# flash.net
KiCad netlist of a schematic drawn in Altium Designer
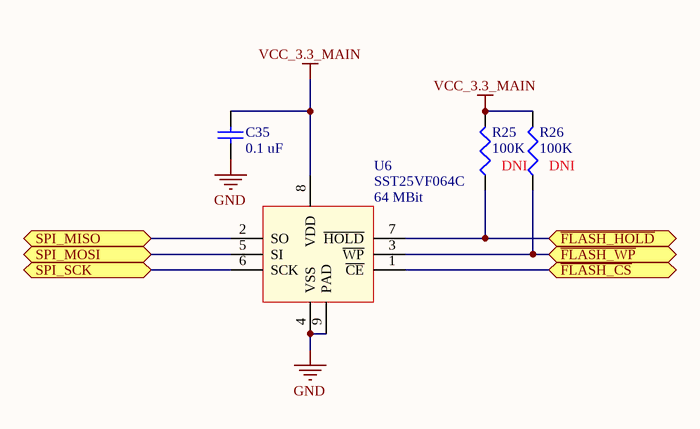
[diagram p0: flash.SchDoc]

(export (version "E")
  (design (tool "Eeschema 10.0.6"))
  (components
    (comp (ref "C35")
      (value "0.1 uF")
      (footprint "0402")
      (description "Ceramic capacitor, 0.1u, 0402 package")
      (fields (field (name "TOLERANCE") "10%") (field (name "Comment") "Ceramic capacitor"))
      (libsource (lib "rlc") (part "C_0.1u_10V_0402_ceramic"))
    )
    (comp (ref "R25")
      (value "100K")
      (footprint "0402")
      (description "Chip resistor, 100K, 0402 package")
      (fields (field (name "TOLERANCE") "1%") (field (name "POWER") "1/16 W"))
      (libsource (lib "rlc") (part "R_100K_0402"))
    )
    (comp (ref "R26")
      (value "100K")
      (footprint "0402")
      (description "Chip resistor, 100K, 0402 package")
      (fields (field (name "TOLERANCE") "1%") (field (name "POWER") "1/16 W"))
      (libsource (lib "rlc") (part "R_100K_0402"))
    )
    (comp (ref "U6")
      (value "SST25VF064C")
      (footprint "WSON")
      (description "64 Mbit SPI Serial Dual I/O Flash")
      (fields (field (name "CAPACITY") "64 MBit"))
      (libsource (lib "sdl") (part "SST25VF064C"))
    )
  )
  (nets
    (net (code "1") (name "/SPI_MISO") (class "Default")
      (node (ref "U6") (pin "2") (pinfunction "SO_2") (pintype "passive"))
    )
    (net (code "2") (name "/SPI_MOSI") (class "Default")
      (node (ref "U6") (pin "5") (pinfunction "SI_5") (pintype "passive"))
    )
    (net (code "3") (name "/SPI_SCK") (class "Default")
      (node (ref "U6") (pin "6") (pinfunction "SCK_6") (pintype "passive"))
    )
    (net (code "4") (name "/~{FLASH_CS}") (class "Default")
      (node (ref "U6") (pin "1") (pinfunction "~{CE}_1") (pintype "passive"))
    )
    (net (code "5") (name "/~{FLASH_HOLD}") (class "Default")
      (node (ref "R25") (pin "2") (pintype "passive"))
      (node (ref "U6") (pin "7") (pinfunction "~{HOLD}_7") (pintype "passive"))
    )
    (net (code "6") (name "/~{FLASH_WP}") (class "Default")
      (node (ref "R26") (pin "2") (pintype "passive"))
      (node (ref "U6") (pin "3") (pinfunction "~{WP}_3") (pintype "passive"))
    )
    (net (code "7") (name "GND") (class "Default")
      (node (ref "C35") (pin "2") (pintype "passive"))
      (node (ref "U6") (pin "4") (pinfunction "VSS_4") (pintype "passive"))
      (node (ref "U6") (pin "9") (pinfunction "PAD_9") (pintype "passive"))
    )
    (net (code "8") (name "VCC_3.3_MAIN") (class "Default")
      (node (ref "C35") (pin "1") (pintype "passive"))
      (node (ref "R25") (pin "1") (pintype "passive"))
      (node (ref "R26") (pin "1") (pintype "passive"))
      (node (ref "U6") (pin "8") (pinfunction "VDD_8") (pintype "passive"))
    )
  )
)
